# Main.net
KiCad netlist of a schematic drawn in EAGLE
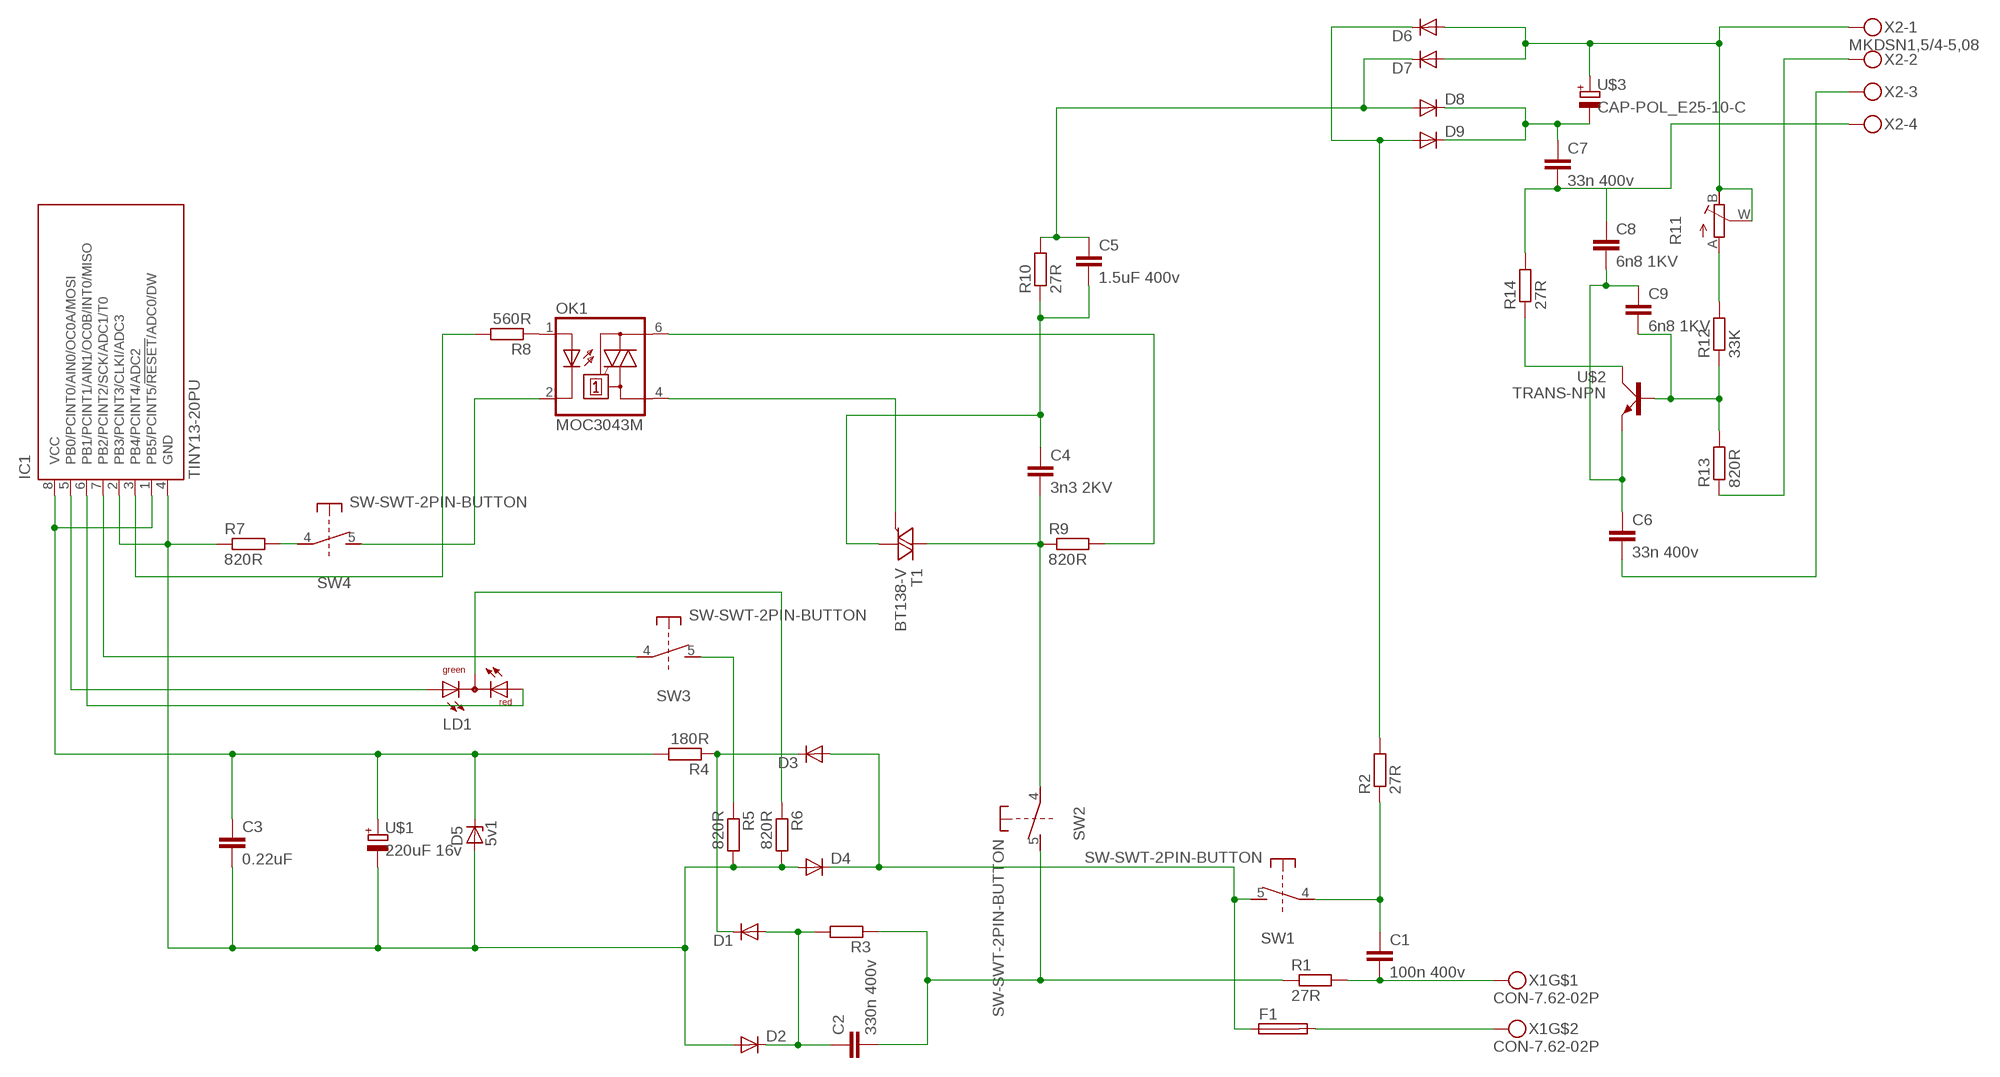
[diagram p0: schematic, sheet 1]

(export (version "E")
  (design (tool "Eeschema 10.0.6"))
  (components
    (comp (ref "C1")
      (value "100n 400v")
      (footprint "eagle-import:C375-155X418")
      (libsource (lib "eagle-import") (part "C-EU375-155X418"))
    )
    (comp (ref "C2")
      (value "330n 400v")
      (footprint "eagle-import:C375-155X418")
      (libsource (lib "eagle-import") (part "C-EU375-155X418"))
    )
    (comp (ref "C3")
      (value "0.22uF")
      (footprint "eagle-import:C050-024X044")
      (libsource (lib "eagle-import") (part "CAP_C50-024X044"))
    )
    (comp (ref "C4")
      (value "3n3 2KV")
      (footprint "eagle-import:C050-024X044")
      (libsource (lib "eagle-import") (part "CAP_C50-024X044"))
    )
    (comp (ref "C5")
      (value "1.5uF 400v")
      (footprint "eagle-import:C375-155X418")
      (libsource (lib "eagle-import") (part "C-EU375-155X418"))
    )
    (comp (ref "C6")
      (value "33n 400v")
      (footprint "eagle-import:C375-155X418")
      (libsource (lib "eagle-import") (part "C-EU375-155X418"))
    )
    (comp (ref "C7")
      (value "33n 400v")
      (footprint "eagle-import:C375-155X418")
      (libsource (lib "eagle-import") (part "C-EU375-155X418"))
    )
    (comp (ref "C8")
      (value "6n8 1KV")
      (footprint "eagle-import:C050-024X044")
      (libsource (lib "eagle-import") (part "CAP_C50-024X044"))
    )
    (comp (ref "C9")
      (value "6n8 1KV")
      (footprint "eagle-import:C050-024X044")
      (libsource (lib "eagle-import") (part "CAP_C50-024X044"))
    )
    (comp (ref "D1")
      (value "DIODE_DO-201")
      (footprint "eagle-import:DO201-15")
      (libsource (lib "eagle-import") (part "DIODE_DO-201"))
    )
    (comp (ref "D2")
      (value "DIODE_DO-201")
      (footprint "eagle-import:DO201-15")
      (libsource (lib "eagle-import") (part "DIODE_DO-201"))
    )
    (comp (ref "D3")
      (value "DIODE_DO-201")
      (footprint "eagle-import:DO201-15")
      (libsource (lib "eagle-import") (part "DIODE_DO-201"))
    )
    (comp (ref "D4")
      (value "DIODE_DO-201")
      (footprint "eagle-import:DO201-15")
      (libsource (lib "eagle-import") (part "DIODE_DO-201"))
    )
    (comp (ref "D5")
      (value "5v1")
      (footprint "eagle-import:DO35Z10")
      (libsource (lib "eagle-import") (part "ZENER-DIODEDO35Z10"))
    )
    (comp (ref "D6")
      (value "DIODE_DO-201")
      (footprint "eagle-import:DO201-15")
      (libsource (lib "eagle-import") (part "DIODE_DO-201"))
    )
    (comp (ref "D7")
      (value "DIODE_DO-201")
      (footprint "eagle-import:DO201-15")
      (libsource (lib "eagle-import") (part "DIODE_DO-201"))
    )
    (comp (ref "D8")
      (value "DIODE_DO-201")
      (footprint "eagle-import:DO201-15")
      (libsource (lib "eagle-import") (part "DIODE_DO-201"))
    )
    (comp (ref "D9")
      (value "DIODE_DO-201")
      (footprint "eagle-import:DO201-15")
      (libsource (lib "eagle-import") (part "DIODE_DO-201"))
    )
    (comp (ref "F1")
      (value "SH22,5")
      (footprint "eagle-import:SH22,5")
      (fields (field (name "MF") "SCHURTER") (field (name "MPN") "0031.8201"))
      (libsource (lib "eagle-import") (part "SH22,5"))
    )
    (comp (ref "IC1")
      (value "TINY13-20PU")
      (footprint "eagle-import:DIL08")
      (fields (field (name "MPN") "ATTINY13-20PU"))
      (libsource (lib "eagle-import") (part "TINY13PU-20"))
    )
    (comp (ref "LD1")
      (value "DUOLED-RG-C")
      (footprint "eagle-import:DUOLED-C-5MM")
      (libsource (lib "eagle-import") (part "DUOLED-RG-C"))
    )
    (comp (ref "OK1")
      (value "MOC3043M")
      (footprint "eagle-import:DIL06")
      (fields (field (name "MF") "FAIRCHILD SEMICONDUCTOR") (field (name "MPN") "MOC3043-M"))
      (libsource (lib "eagle-import") (part "MOC3043M"))
    )
    (comp (ref "R1")
      (value "27R")
      (footprint "eagle-import:MF-2")
      (libsource (lib "eagle-import") (part "R_MF-2"))
    )
    (comp (ref "R2")
      (value "27R")
      (footprint "eagle-import:MF-2")
      (libsource (lib "eagle-import") (part "R_MF-2"))
    )
    (comp (ref "R3")
      (value "R_MF-2")
      (footprint "eagle-import:MF-2")
      (libsource (lib "eagle-import") (part "R_MF-2"))
    )
    (comp (ref "R4")
      (value "180R")
      (footprint "eagle-import:MF-2")
      (libsource (lib "eagle-import") (part "R_MF-2"))
    )
    (comp (ref "R5")
      (value "820R")
      (footprint "eagle-import:MF-2")
      (libsource (lib "eagle-import") (part "R_MF-2"))
    )
    (comp (ref "R6")
      (value "820R")
      (footprint "eagle-import:MF-2")
      (libsource (lib "eagle-import") (part "R_MF-2"))
    )
    (comp (ref "R7")
      (value "820R")
      (footprint "eagle-import:MF-2")
      (libsource (lib "eagle-import") (part "R_MF-2"))
    )
    (comp (ref "R8")
      (value "560R")
      (footprint "eagle-import:MF-2")
      (libsource (lib "eagle-import") (part "R_MF-2"))
    )
    (comp (ref "R9")
      (value "820R")
      (footprint "eagle-import:MF-2")
      (libsource (lib "eagle-import") (part "R_MF-2"))
    )
    (comp (ref "R10")
      (value "27R")
      (footprint "eagle-import:MF-2")
      (libsource (lib "eagle-import") (part "R_MF-2"))
    )
    (comp (ref "R11")
      (value "R_POTTURN-X")
      (footprint "eagle-import:RJ9W")
      (libsource (lib "eagle-import") (part "R_POTTURN-X"))
    )
    (comp (ref "R12")
      (value "33K")
      (footprint "eagle-import:MF-2")
      (libsource (lib "eagle-import") (part "R_MF-2"))
    )
    (comp (ref "R13")
      (value "820R")
      (footprint "eagle-import:MF-2")
      (libsource (lib "eagle-import") (part "R_MF-2"))
    )
    (comp (ref "R14")
      (value "27R")
      (footprint "eagle-import:MF-2")
      (libsource (lib "eagle-import") (part "R_MF-2"))
    )
    (comp (ref "SW1")
      (value "SW-SWT-2PIN-BUTTON")
      (footprint "eagle-import:SWT-2-2PIN-WBUTTON")
      (libsource (lib "eagle-import") (part "SW-SWT-2PIN-BUTTON"))
    )
    (comp (ref "SW2")
      (value "SW-SWT-2PIN-BUTTON")
      (footprint "eagle-import:SWT-2-2PIN-WBUTTON")
      (libsource (lib "eagle-import") (part "SW-SWT-2PIN-BUTTON"))
    )
    (comp (ref "SW3")
      (value "SW-SWT-2PIN-BUTTON")
      (footprint "eagle-import:SWT-2-2PIN-WBUTTON")
      (libsource (lib "eagle-import") (part "SW-SWT-2PIN-BUTTON"))
    )
    (comp (ref "SW4")
      (value "SW-SWT-2PIN-BUTTON")
      (footprint "eagle-import:SWT-2-2PIN-WBUTTON")
      (libsource (lib "eagle-import") (part "SW-SWT-2PIN-BUTTON"))
    )
    (comp (ref "T1")
      (value "BT138-V")
      (footprint "eagle-import:TO220BV")
      (libsource (lib "eagle-import") (part "BT138-V"))
    )
    (comp (ref "U$1")
      (value "220uF 16v")
      (footprint "eagle-import:E3,5-8")
      (libsource (lib "eagle-import") (part "CAP-POL_E3.5-8"))
    )
    (comp (ref "U$2")
      (value "TRANS-NPN")
      (footprint "eagle-import:SOT-92WIDE")
      (libsource (lib "eagle-import") (part "TRANS-NPN"))
    )
    (comp (ref "U$3")
      (value "CAP-POL_E25-10-C")
      (footprint "eagle-import:C_D25-G10-CLAMP")
      (libsource (lib "eagle-import") (part "CAP-POL_E25-10-C"))
    )
    (comp (ref "X1")
      (value "CON-7.62-02P")
      (footprint "eagle-import:KF25C-7.62-02P-13")
      (libsource (lib "eagle-import") (part "CON-7.62-02P"))
    )
    (comp (ref "X2")
      (value "MKDSN1,5/4-5,08")
      (footprint "eagle-import:MKDSN1,5_4-5,08")
      (libsource (lib "eagle-import") (part "MKDSN1,5/4-5,08"))
    )
  )
  (nets
    (net (code "1") (name "Net-(C2-Pad1)") (class "Default")
      (node (ref "C2") (pin "1") (pinfunction "1_1") (pintype "passive"))
      (node (ref "D1") (pin "A") (pinfunction "A_A") (pintype "passive"))
      (node (ref "D2") (pin "C") (pinfunction "C_C") (pintype "passive"))
      (node (ref "R3") (pin "2") (pinfunction "2_2") (pintype "passive"))
    )
    (net (code "2") (name "Net-(C5-Pad1)") (class "Default")
      (node (ref "C5") (pin "1") (pinfunction "1_1") (pintype "passive"))
      (node (ref "D7") (pin "C") (pinfunction "C_C") (pintype "passive"))
      (node (ref "D8") (pin "A") (pinfunction "A_A") (pintype "passive"))
      (node (ref "R10") (pin "2") (pinfunction "2_2") (pintype "passive"))
    )
    (net (code "3") (name "Net-(C6-Pad1)") (class "Default")
      (node (ref "C6") (pin "1") (pinfunction "1_1") (pintype "passive"))
      (node (ref "C8") (pin "2") (pinfunction "2_2") (pintype "passive"))
      (node (ref "C9") (pin "1") (pinfunction "1_1") (pintype "passive"))
      (node (ref "U$2") (pin "E") (pinfunction "E_E") (pintype "passive"))
    )
    (net (code "4") (name "Net-(C7-Pad1)") (class "Default")
      (node (ref "C7") (pin "1") (pinfunction "1_1") (pintype "passive"))
      (node (ref "D8") (pin "C") (pinfunction "C_C") (pintype "passive"))
      (node (ref "D9") (pin "C") (pinfunction "C_C") (pintype "passive"))
      (node (ref "U$3") (pin "-") (pinfunction "-_-") (pintype "passive"))
    )
    (net (code "5") (name "Net-(C9-Pad2)") (class "Default")
      (node (ref "C9") (pin "2") (pinfunction "2_2") (pintype "passive"))
      (node (ref "R12") (pin "1") (pinfunction "1_1") (pintype "passive"))
      (node (ref "R13") (pin "2") (pinfunction "2_2") (pintype "passive"))
      (node (ref "U$2") (pin "B") (pinfunction "B_B") (pintype "passive"))
    )
    (net (code "6") (name "Net-(D1-PadC)") (class "Default")
      (node (ref "D1") (pin "C") (pinfunction "C_C") (pintype "passive"))
      (node (ref "D3") (pin "C") (pinfunction "C_C") (pintype "passive"))
      (node (ref "R4") (pin "1") (pinfunction "1_1") (pintype "passive"))
    )
    (net (code "7") (name "Net-(D6-PadC)") (class "Default")
      (node (ref "D6") (pin "C") (pinfunction "C_C") (pintype "passive"))
      (node (ref "D9") (pin "A") (pinfunction "A_A") (pintype "passive"))
      (node (ref "R2") (pin "2") (pinfunction "2_2") (pintype "passive"))
    )
    (net (code "8") (name "Net-(IC1-GND)") (class "Default")
      (node (ref "C3") (pin "2") (pinfunction "2_2") (pintype "passive"))
      (node (ref "D2") (pin "A") (pinfunction "A_A") (pintype "passive"))
      (node (ref "D4") (pin "A") (pinfunction "A_A") (pintype "passive"))
      (node (ref "D5") (pin "A") (pinfunction "A_A") (pintype "passive"))
      (node (ref "IC1") (pin "2") (pinfunction "PB3/PCINT3/CLKI/ADC3_2") (pintype "bidirectional"))
      (node (ref "IC1") (pin "4") (pinfunction "GND_4") (pintype "power_in"))
      (node (ref "R5") (pin "2") (pinfunction "2_2") (pintype "passive"))
      (node (ref "R6") (pin "2") (pinfunction "2_2") (pintype "passive"))
      (node (ref "R7") (pin "1") (pinfunction "1_1") (pintype "passive"))
      (node (ref "U$1") (pin "-") (pinfunction "-_-") (pintype "passive"))
    )
    (net (code "9") (name "Net-(IC1-PB0{slash}PCINT0{slash}AIN0{slash}OC0A{slash}MOSI)") (class "Default")
      (node (ref "IC1") (pin "5") (pinfunction "PB0/PCINT0/AIN0/OC0A/MOSI_5") (pintype "bidirectional"))
      (node (ref "LD1") (pin "AX") (pinfunction "AG_AX") (pintype "passive"))
    )
    (net (code "10") (name "Net-(IC1-PB1{slash}PCINT1{slash}AIN1{slash}OC0B{slash}INT0{slash}MISO)") (class "Default")
      (node (ref "IC1") (pin "6") (pinfunction "PB1/PCINT1/AIN1/OC0B/INT0/MISO_6") (pintype "bidirectional"))
      (node (ref "LD1") (pin "AR") (pinfunction "AR_AR") (pintype "passive"))
    )
    (net (code "11") (name "Net-(IC1-PB2{slash}PCINT2{slash}SCK{slash}ADC1{slash}T0)") (class "Default")
      (node (ref "IC1") (pin "7") (pinfunction "PB2/PCINT2/SCK/ADC1/T0_7") (pintype "bidirectional"))
      (node (ref "SW3") (pin "4") (pinfunction "2_4") (pintype "passive"))
    )
    (net (code "12") (name "Net-(IC1-PB4{slash}PCINT4{slash}ADC2)") (class "Default")
      (node (ref "IC1") (pin "3") (pinfunction "PB4/PCINT4/ADC2_3") (pintype "bidirectional"))
      (node (ref "R8") (pin "2") (pinfunction "2_2") (pintype "passive"))
    )
    (net (code "13") (name "Net-(IC1-PB5{slash}PCINT5{slash}~{RESET}{slash}ADC0{slash}DW)") (class "Default")
      (node (ref "C3") (pin "1") (pinfunction "1_1") (pintype "passive"))
      (node (ref "D5") (pin "C") (pinfunction "C_C") (pintype "passive"))
      (node (ref "IC1") (pin "1") (pinfunction "PB5/PCINT5/~{RESET}/ADC0/DW_1") (pintype "bidirectional"))
      (node (ref "IC1") (pin "8") (pinfunction "VCC_8") (pintype "power_in"))
      (node (ref "R4") (pin "2") (pinfunction "2_2") (pintype "passive"))
      (node (ref "U$1") (pin "+") (pinfunction "+_+") (pintype "passive"))
    )
    (net (code "14") (name "Net-(LD1-PadC)") (class "Default")
      (node (ref "LD1") (pin "C") (pinfunction "C_C") (pintype "passive"))
      (node (ref "R6") (pin "1") (pinfunction "1_1") (pintype "passive"))
    )
    (net (code "15") (name "Net-(OK1-A)") (class "Default")
      (node (ref "OK1") (pin "1") (pinfunction "A_1") (pintype "passive"))
      (node (ref "R8") (pin "1") (pinfunction "1_1") (pintype "passive"))
    )
    (net (code "16") (name "Net-(OK1-A1)") (class "Default")
      (node (ref "OK1") (pin "4") (pinfunction "A1_4") (pintype "passive"))
      (node (ref "T1") (pin "G") (pinfunction "G_G") (pintype "passive"))
    )
    (net (code "17") (name "Net-(OK1-A2)") (class "Default")
      (node (ref "OK1") (pin "6") (pinfunction "A2_6") (pintype "passive"))
      (node (ref "R9") (pin "2") (pinfunction "2_2") (pintype "passive"))
    )
    (net (code "18") (name "Net-(OK1-C)") (class "Default")
      (node (ref "OK1") (pin "2") (pinfunction "C_2") (pintype "passive"))
      (node (ref "SW4") (pin "5") (pinfunction "3_5") (pintype "passive"))
    )
    (net (code "19") (name "Net-(R11-E)") (class "Default")
      (node (ref "D6") (pin "A") (pinfunction "A_A") (pintype "passive"))
      (node (ref "D7") (pin "A") (pinfunction "A_A") (pintype "passive"))
      (node (ref "R11") (pin "B") (pinfunction "E_B") (pintype "passive"))
      (node (ref "R11") (pin "W") (pinfunction "S_W") (pintype "passive"))
      (node (ref "U$3") (pin "+") (pinfunction "+_+") (pintype "passive"))
      (node (ref "X2") (pin "1") (pinfunction "KL_1") (pintype "passive"))
    )
    (net (code "20") (name "Net-(R11-PadA)") (class "Default")
      (node (ref "R11") (pin "A") (pinfunction "A_A") (pintype "passive"))
      (node (ref "R12") (pin "2") (pinfunction "2_2") (pintype "passive"))
    )
    (net (code "21") (name "Net-(R14-Pad1)") (class "Default")
      (node (ref "R14") (pin "1") (pinfunction "1_1") (pintype "passive"))
      (node (ref "U$2") (pin "C") (pinfunction "C_C") (pintype "passive"))
    )
    (net (code "22") (name "Net-(SW1-2)") (class "Default")
      (node (ref "C1") (pin "1") (pinfunction "1_1") (pintype "passive"))
      (node (ref "R2") (pin "1") (pinfunction "1_1") (pintype "passive"))
      (node (ref "SW1") (pin "4") (pinfunction "2_4") (pintype "passive"))
    )
    (net (code "23") (name "Net-(SW1-3)") (class "Default")
      (node (ref "D3") (pin "A") (pinfunction "A_A") (pintype "passive"))
      (node (ref "D4") (pin "C") (pinfunction "C_C") (pintype "passive"))
      (node (ref "F1") (pin "1") (pinfunction "1_1") (pintype "passive"))
      (node (ref "SW1") (pin "5") (pinfunction "3_5") (pintype "passive"))
    )
    (net (code "24") (name "Net-(SW2-2)") (class "Default")
      (node (ref "C4") (pin "2") (pinfunction "2_2") (pintype "passive"))
      (node (ref "R9") (pin "1") (pinfunction "1_1") (pintype "passive"))
      (node (ref "SW2") (pin "4") (pinfunction "2_4") (pintype "passive"))
      (node (ref "T1") (pin "T2") (pinfunction "A2_T2") (pintype "passive"))
    )
    (net (code "25") (name "Net-(SW2-3)") (class "Default")
      (node (ref "C2") (pin "2") (pinfunction "2_2") (pintype "passive"))
      (node (ref "R1") (pin "1") (pinfunction "1_1") (pintype "passive"))
      (node (ref "R3") (pin "1") (pinfunction "1_1") (pintype "passive"))
      (node (ref "SW2") (pin "5") (pinfunction "3_5") (pintype "passive"))
    )
    (net (code "26") (name "Net-(SW3-3)") (class "Default")
      (node (ref "R5") (pin "1") (pinfunction "1_1") (pintype "passive"))
      (node (ref "SW3") (pin "5") (pinfunction "3_5") (pintype "passive"))
    )
    (net (code "27") (name "Net-(SW4-2)") (class "Default")
      (node (ref "R7") (pin "2") (pinfunction "2_2") (pintype "passive"))
      (node (ref "SW4") (pin "4") (pinfunction "2_4") (pintype "passive"))
    )
    (net (code "28") (name "Net-(T1-A1)") (class "Default")
      (node (ref "C4") (pin "1") (pinfunction "1_1") (pintype "passive"))
      (node (ref "C5") (pin "2") (pinfunction "2_2") (pintype "passive"))
      (node (ref "R10") (pin "1") (pinfunction "1_1") (pintype "passive"))
      (node (ref "T1") (pin "T1") (pinfunction "A1_T1") (pintype "passive"))
    )
    (net (code "29") (name "Net-(X1A-KL)") (class "Default")
      (node (ref "C1") (pin "2") (pinfunction "2_2") (pintype "passive"))
      (node (ref "R1") (pin "2") (pinfunction "2_2") (pintype "passive"))
      (node (ref "X1") (pin "P$1") (pinfunction "KL_P$1") (pintype "passive"))
    )
    (net (code "30") (name "Net-(X1B-KL)") (class "Default")
      (node (ref "F1") (pin "2") (pinfunction "2_2") (pintype "passive"))
      (node (ref "X1") (pin "P$2") (pinfunction "KL_P$2") (pintype "passive"))
    )
    (net (code "31") (name "Net-(X2B-KL)") (class "Default")
      (node (ref "R13") (pin "1") (pinfunction "1_1") (pintype "passive"))
      (node (ref "X2") (pin "2") (pinfunction "KL_2") (pintype "passive"))
    )
    (net (code "32") (name "Net-(X2C-KL)") (class "Default")
      (node (ref "C6") (pin "2") (pinfunction "2_2") (pintype "passive"))
      (node (ref "X2") (pin "3") (pinfunction "KL_3") (pintype "passive"))
    )
    (net (code "33") (name "Net-(X2D-KL)") (class "Default")
      (node (ref "C7") (pin "2") (pinfunction "2_2") (pintype "passive"))
      (node (ref "C8") (pin "1") (pinfunction "1_1") (pintype "passive"))
      (node (ref "R14") (pin "2") (pinfunction "2_2") (pintype "passive"))
      (node (ref "X2") (pin "4") (pinfunction "KL_4") (pintype "passive"))
    )
  )
)
